# Breadboard-ATTINY84.net
KiCad netlist of a schematic drawn in EAGLE
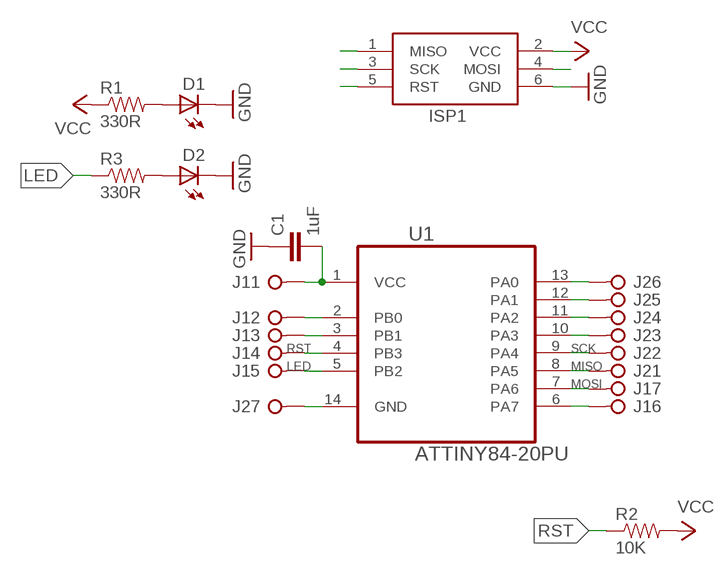
[diagram p0: schematic, sheet 1]

(export (version "E")
  (design (tool "Eeschema 10.0.6"))
  (components
    (comp (ref "C1")
      (value "1uF")
      (footprint "eagle-import:CAPACITOR-0805")
      (libsource (lib "eagle-import") (part "CAPACITOR-0805"))
    )
    (comp (ref "D1")
      (value "LED-0805")
      (footprint "eagle-import:LED-0805")
      (libsource (lib "eagle-import") (part "LED-0805"))
    )
    (comp (ref "D2")
      (value "LED-0805")
      (footprint "eagle-import:LED-0805")
      (libsource (lib "eagle-import") (part "LED-0805"))
    )
    (comp (ref "ISP1")
      (value "ICSP-HEADER-6")
      (footprint "eagle-import:ICSP-HEADER")
      (libsource (lib "eagle-import") (part "ICSP-HEADER-6"))
    )
    (comp (ref "J1")
      (value "PINHD-1X7")
      (footprint "eagle-import:1X07")
      (libsource (lib "eagle-import") (part "PINHD-1X7"))
    )
    (comp (ref "J2")
      (value "PINHD-1X7")
      (footprint "eagle-import:1X07")
      (libsource (lib "eagle-import") (part "PINHD-1X7"))
    )
    (comp (ref "R1")
      (value "330R")
      (footprint "eagle-import:RESISTOR-0805")
      (libsource (lib "eagle-import") (part "RESISTOR-0805"))
    )
    (comp (ref "R2")
      (value "10K")
      (footprint "eagle-import:RESISTOR-0805")
      (libsource (lib "eagle-import") (part "RESISTOR-0805"))
    )
    (comp (ref "R3")
      (value "330R")
      (footprint "eagle-import:RESISTOR-0805")
      (libsource (lib "eagle-import") (part "RESISTOR-0805"))
    )
    (comp (ref "U1")
      (value "ATTINY84-20PU")
      (footprint "eagle-import:DIP14")
      (libsource (lib "eagle-import") (part "ATTINY84-20PU"))
    )
  )
  (nets
    (net (code "1") (name "/MISO") (class "Default")
      (node (ref "ISP1") (pin "1") (pinfunction "MISO_1") (pintype "input"))
      (node (ref "J2") (pin "1") (pinfunction "KL_1") (pintype "passive"))
      (node (ref "U1") (pin "8") (pinfunction "PA5_8") (pintype "bidirectional"))
    )
    (net (code "2") (name "/MOSI") (class "Default")
      (node (ref "ISP1") (pin "4") (pinfunction "MOSI_4") (pintype "output"))
      (node (ref "J1") (pin "7") (pinfunction "KL_7") (pintype "passive"))
      (node (ref "U1") (pin "7") (pinfunction "PA6_7") (pintype "bidirectional"))
    )
    (net (code "3") (name "/SCK") (class "Default")
      (node (ref "ISP1") (pin "3") (pinfunction "SCK_3") (pintype "output"))
      (node (ref "J2") (pin "2") (pinfunction "KL_2") (pintype "passive"))
      (node (ref "U1") (pin "9") (pinfunction "PA4_9") (pintype "bidirectional"))
    )
    (net (code "4") (name "GND") (class "Default")
      (node (ref "C1") (pin "1") (pinfunction "1_1") (pintype "passive"))
      (node (ref "D1") (pin "2") (pinfunction "C_2") (pintype "passive"))
      (node (ref "D2") (pin "2") (pinfunction "C_2") (pintype "passive"))
      (node (ref "ISP1") (pin "6") (pinfunction "GND_6") (pintype "power_in"))
      (node (ref "J2") (pin "7") (pinfunction "KL_7") (pintype "passive"))
      (node (ref "U1") (pin "14") (pinfunction "GND_14") (pintype "passive"))
    )
    (net (code "5") (name "LED") (class "Default")
      (node (ref "J1") (pin "5") (pinfunction "KL_5") (pintype "passive"))
      (node (ref "R3") (pin "1") (pinfunction "1_1") (pintype "passive"))
      (node (ref "U1") (pin "5") (pinfunction "PB2_5") (pintype "bidirectional"))
    )
    (net (code "6") (name "Net-(D1-A)") (class "Default")
      (node (ref "D1") (pin "1") (pinfunction "A_1") (pintype "passive"))
      (node (ref "R1") (pin "2") (pinfunction "2_2") (pintype "passive"))
    )
    (net (code "7") (name "Net-(D2-A)") (class "Default")
      (node (ref "D2") (pin "1") (pinfunction "A_1") (pintype "passive"))
      (node (ref "R3") (pin "2") (pinfunction "2_2") (pintype "passive"))
    )
    (net (code "8") (name "Net-(J1B-KL)") (class "Default")
      (node (ref "J1") (pin "2") (pinfunction "KL_2") (pintype "passive"))
      (node (ref "U1") (pin "2") (pinfunction "PB0_2") (pintype "bidirectional"))
    )
    (net (code "9") (name "Net-(J1C-KL)") (class "Default")
      (node (ref "J1") (pin "3") (pinfunction "KL_3") (pintype "passive"))
      (node (ref "U1") (pin "3") (pinfunction "PB1_3") (pintype "bidirectional"))
    )
    (net (code "10") (name "Net-(J1F-KL)") (class "Default")
      (node (ref "J1") (pin "6") (pinfunction "KL_6") (pintype "passive"))
      (node (ref "U1") (pin "6") (pinfunction "PA7_6") (pintype "bidirectional"))
    )
    (net (code "11") (name "Net-(J2C-KL)") (class "Default")
      (node (ref "J2") (pin "3") (pinfunction "KL_3") (pintype "passive"))
      (node (ref "U1") (pin "10") (pinfunction "PA3_10") (pintype "bidirectional"))
    )
    (net (code "12") (name "Net-(J2D-KL)") (class "Default")
      (node (ref "J2") (pin "4") (pinfunction "KL_4") (pintype "passive"))
      (node (ref "U1") (pin "11") (pinfunction "PA2_11") (pintype "bidirectional"))
    )
    (net (code "13") (name "Net-(J2E-KL)") (class "Default")
      (node (ref "J2") (pin "5") (pinfunction "KL_5") (pintype "passive"))
      (node (ref "U1") (pin "12") (pinfunction "PA1_12") (pintype "bidirectional"))
    )
    (net (code "14") (name "Net-(J2F-KL)") (class "Default")
      (node (ref "J2") (pin "6") (pinfunction "KL_6") (pintype "passive"))
      (node (ref "U1") (pin "13") (pinfunction "PA0_13") (pintype "bidirectional"))
    )
    (net (code "15") (name "RST") (class "Default")
      (node (ref "ISP1") (pin "5") (pinfunction "RST_5") (pintype "output"))
      (node (ref "J1") (pin "4") (pinfunction "KL_4") (pintype "passive"))
      (node (ref "R2") (pin "1") (pinfunction "1_1") (pintype "passive"))
      (node (ref "U1") (pin "4") (pinfunction "PB3_4") (pintype "bidirectional"))
    )
    (net (code "16") (name "VCC") (class "Default")
      (node (ref "C1") (pin "2") (pinfunction "2_2") (pintype "passive"))
      (node (ref "ISP1") (pin "2") (pinfunction "VCC_2") (pintype "power_in"))
      (node (ref "J1") (pin "1") (pinfunction "KL_1") (pintype "passive"))
      (node (ref "R1") (pin "1") (pinfunction "1_1") (pintype "passive"))
      (node (ref "R2") (pin "2") (pinfunction "2_2") (pintype "passive"))
      (node (ref "U1") (pin "1") (pinfunction "VCC_1") (pintype "power_in"))
    )
  )
)
